# microcontroller_common.net
KiCad netlist of a schematic drawn in Altium Designer
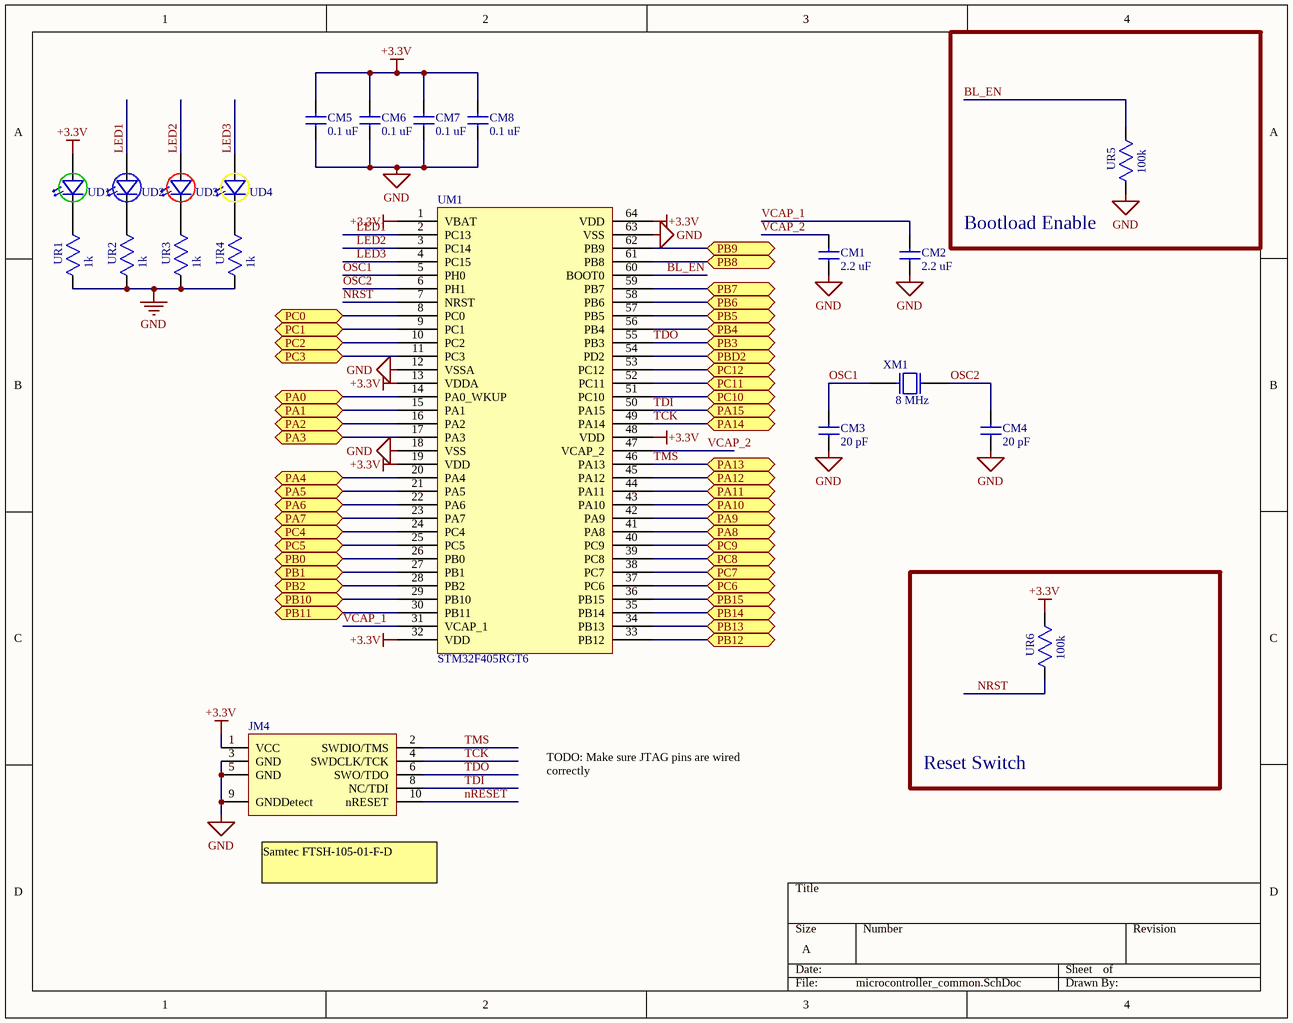
[diagram p0: microcontroller_common.SchDoc]

(export (version "E")
  (design (tool "Eeschema 10.0.6"))
  (components
    (comp (ref "CM1")
      (value "2.2 uF")
      (footprint "0805_Capacitor")
      (description "CAP CERM 2.2 uF")
      (fields (field (name "Comment") "CAP 2.2 uF"))
      (libsource (lib "d1_SchLib") (part "C_0805_2.2uF"))
    )
    (comp (ref "CM2")
      (value "2.2 uF")
      (footprint "0805_Capacitor")
      (description "CAP CERM 2.2 uF")
      (fields (field (name "Comment") "CAP 2.2 uF"))
      (libsource (lib "d1_SchLib") (part "C_0805_2.2uF"))
    )
    (comp (ref "CM3")
      (value "20 pF")
      (footprint "0805_Capacitor")
      (description "CAP CERM 20PF 5% 100V NP0 0805")
      (fields
        (field (name "MANUFACTURER") "AVX")
        (field (name "Comment") "CAP 20PF")
        (field (name "SVP CREATOR") "Jonathan Nutzmann")
      )
      (libsource (lib "d1_SchLib") (part "C_0805_20PF_100V_5%"))
    )
    (comp (ref "CM4")
      (value "20 pF")
      (footprint "0805_Capacitor")
      (description "CAP CERM 20PF 5% 100V NP0 0805")
      (fields
        (field (name "MANUFACTURER") "AVX")
        (field (name "Comment") "CAP 20PF")
        (field (name "SVP CREATOR") "Jonathan Nutzmann")
      )
      (libsource (lib "d1_SchLib") (part "C_0805_20PF_100V_5%"))
    )
    (comp (ref "CM5")
      (value "0.1 uF")
      (footprint "0805_Capacitor")
      (description "CAP CERM 0.1uF")
      (fields
        (field (name "MANUFACTURER") "Yageo")
        (field (name "Comment") "CAP 0.1uF")
        (field (name "SVP CREATOR") "Brett Paulsen")
      )
      (libsource (lib "d1_SchLib") (part "C_0805_0.1uF"))
    )
    (comp (ref "CM6")
      (value "0.1 uF")
      (footprint "0805_Capacitor")
      (description "CAP CERM 0.1uF")
      (fields
        (field (name "MANUFACTURER") "Yageo")
        (field (name "Comment") "CAP 0.1uF")
        (field (name "SVP CREATOR") "Brett Paulsen")
      )
      (libsource (lib "d1_SchLib") (part "C_0805_0.1uF"))
    )
    (comp (ref "CM7")
      (value "0.1 uF")
      (footprint "0805_Capacitor")
      (description "CAP CERM 0.1uF")
      (fields
        (field (name "MANUFACTURER") "Yageo")
        (field (name "Comment") "CAP 0.1uF")
        (field (name "SVP CREATOR") "Brett Paulsen")
      )
      (libsource (lib "d1_SchLib") (part "C_0805_0.1uF"))
    )
    (comp (ref "CM8")
      (value "0.1 uF")
      (footprint "0805_Capacitor")
      (description "CAP CERM 0.1uF")
      (fields
        (field (name "MANUFACTURER") "Yageo")
        (field (name "Comment") "CAP 0.1uF")
        (field (name "SVP CREATOR") "Brett Paulsen")
      )
      (libsource (lib "d1_SchLib") (part "C_0805_0.1uF"))
    )
    (comp (ref "JM4")
      (value "J_CORTEX_DEBUG")
      (footprint "CORTEX_DEBUG")
      (description "CORTEX JTAG DEBUG CONNECTOR")
      (libsource (lib "Nutz") (part "J_CORTEX_DEBUG"))
    )
    (comp (ref "UD1")
      (value "D_LED_0805_GREEN")
      (footprint "0805P_Green")
      (description "LED CHIPLED 570NM GREEN 0805 SMD")
      (fields
        (field (name "MANUFACTURER") "Osram Opto Semiconductors Inc")
        (field (name "SVP CREATOR") "Nate Bolyard")
        (field (name "SVP REVIEWER 1") "Trevtron")
      )
      (libsource (lib "d1_SchLib") (part "D_LED_0805_GREEN"))
    )
    (comp (ref "UD2")
      (value "D_LED_0805_BLUE")
      (footprint "0805_BLUE")
      (description "LED 2X1.2MM 470NM BL WTR CLR SMD")
      (fields (field (name "SVP CREATOR") "Jonathan Nutzmann"))
      (libsource (lib "d1_SchLib") (part "D_LED_0805_BLUE"))
    )
    (comp (ref "UD3")
      (value "D_LED_0805_RED")
      (footprint "0805P_RED")
      (description "LED CHIPLED 645NM RED DIFF 0805")
      (fields (field (name "SVP CREATOR") "Jonathan Nutzmann"))
      (libsource (lib "d1_SchLib") (part "D_LED_0805_RED"))
    )
    (comp (ref "UD4")
      (value "D_LED_0805_YELLOW")
      (footprint "0805P_YELLOW")
      (description "LED 595NM AMBER DIFF SMD 0805")
      (fields (field (name "SVP CREATOR") "Jonathan Nutzmann"))
      (libsource (lib "d1_SchLib") (part "D_LED_0805_YELLOW"))
    )
    (comp (ref "UM1")
      (value "STM32F405RGT6")
      (footprint "STM32_LQFP64")
      (description "IC MCU 32BIT 1MB FLASH 64LQFP")
      (fields (field (name "MANUFACTURER") "STMicroelectronics"))
      (libsource (lib "Nutz") (part "U_STM32F405RGT6"))
    )
    (comp (ref "UR1")
      (value "1k")
      (footprint "0805_Resistor")
      (description "RES 1K OHM 1/8W 1% 0805 SMD")
      (fields (field (name "Comment") "R_0805_1k") (field (name "SVP CREATOR") "Katie Moenkhaus"))
      (libsource (lib "d1_SchLib") (part "R_0805_1K_1%"))
    )
    (comp (ref "UR2")
      (value "1k")
      (footprint "0805_Resistor")
      (description "RES 1K OHM 1/8W 1% 0805 SMD")
      (fields (field (name "Comment") "R_0805_1k") (field (name "SVP CREATOR") "Katie Moenkhaus"))
      (libsource (lib "d1_SchLib") (part "R_0805_1K_1%"))
    )
    (comp (ref "UR3")
      (value "1k")
      (footprint "0805_Resistor")
      (description "RES 1K OHM 1/8W 1% 0805 SMD")
      (fields (field (name "Comment") "R_0805_1k") (field (name "SVP CREATOR") "Katie Moenkhaus"))
      (libsource (lib "d1_SchLib") (part "R_0805_1K_1%"))
    )
    (comp (ref "UR4")
      (value "1k")
      (footprint "0805_Resistor")
      (description "RES 1K OHM 1/8W 1% 0805 SMD")
      (fields (field (name "Comment") "R_0805_1k") (field (name "SVP CREATOR") "Katie Moenkhaus"))
      (libsource (lib "d1_SchLib") (part "R_0805_1K_1%"))
    )
    (comp (ref "UR5")
      (value "100k")
      (footprint "0805_Resistor")
      (description "RES 100K OHM 1/8W 1% 0805 SMD")
      (fields
        (field (name "MANUFACTURER") "Rohm Semiconductor")
        (field (name "Comment") "R_0805_100k_1%")
        (field (name "SVP CREATOR") "Jonathan Nutzmann")
      )
      (libsource (lib "d1_SchLib") (part "R_0805_100k_1%"))
    )
    (comp (ref "UR6")
      (value "100k")
      (footprint "0805_Resistor")
      (description "RES 100K OHM 1/8W 1% 0805 SMD")
      (fields
        (field (name "MANUFACTURER") "Rohm Semiconductor")
        (field (name "Comment") "R_0805_100k_1%")
        (field (name "SVP CREATOR") "Jonathan Nutzmann")
      )
      (libsource (lib "d1_SchLib") (part "R_0805_100k_1%"))
    )
    (comp (ref "XM1")
      (value "8 MHz")
      (footprint "HC-49")
      (description "CRYSTAL 8.00 MHZ 20PF 49US")
      (fields
        (field (name "MANUFACTURER") "ECS")
        (field (name "Comment") "HC49")
        (field (name "SVP CREATOR") "Jonathan Nutzmann")
      )
      (libsource (lib "d1_SchLib") (part "X_HC49"))
    )
  )
  (nets
    (net (code "1") (name "+3.3V") (class "Default")
      (node (ref "CM5") (pin "1") (pinfunction "1_1") (pintype "passive"))
      (node (ref "CM6") (pin "1") (pinfunction "1_1") (pintype "passive"))
      (node (ref "CM7") (pin "1") (pinfunction "1_1") (pintype "passive"))
      (node (ref "CM8") (pin "1") (pinfunction "1_1") (pintype "passive"))
      (node (ref "JM4") (pin "1") (pinfunction "VCC_1") (pintype "passive"))
      (node (ref "UD1") (pin "2") (pinfunction "Anode_2") (pintype "passive"))
      (node (ref "UM1") (pin "1") (pinfunction "VBAT_1") (pintype "passive"))
      (node (ref "UM1") (pin "13") (pinfunction "VDDA_13") (pintype "passive"))
      (node (ref "UM1") (pin "19") (pinfunction "VDD_19") (pintype "passive"))
      (node (ref "UM1") (pin "32") (pinfunction "VDD_32") (pintype "passive"))
      (node (ref "UM1") (pin "48") (pinfunction "VDD_48") (pintype "passive"))
      (node (ref "UM1") (pin "64") (pinfunction "VDD_64") (pintype "passive"))
      (node (ref "UR6") (pin "1") (pinfunction "1_1") (pintype "passive"))
    )
    (net (code "2") (name "/BL_EN") (class "Default")
      (node (ref "UM1") (pin "60") (pinfunction "BOOT0_60") (pintype "passive"))
      (node (ref "UR5") (pin "1") (pinfunction "1_1") (pintype "passive"))
    )
    (net (code "3") (name "/LED1") (class "Default")
      (node (ref "UD2") (pin "2") (pinfunction "Anode_2") (pintype "passive"))
      (node (ref "UM1") (pin "2") (pinfunction "PC13_2") (pintype "passive"))
    )
    (net (code "4") (name "/LED2") (class "Default")
      (node (ref "UD3") (pin "2") (pinfunction "Anode_2") (pintype "passive"))
      (node (ref "UM1") (pin "3") (pinfunction "PC14_3") (pintype "passive"))
    )
    (net (code "5") (name "/LED3") (class "Default")
      (node (ref "UD4") (pin "2") (pinfunction "Anode_2") (pintype "passive"))
      (node (ref "UM1") (pin "4") (pinfunction "PC15_4") (pintype "passive"))
    )
    (net (code "6") (name "/NRST") (class "Default")
      (node (ref "UM1") (pin "7") (pinfunction "NRST_7") (pintype "passive"))
      (node (ref "UR6") (pin "2") (pinfunction "2_2") (pintype "passive"))
    )
    (net (code "7") (name "/OSC1") (class "Default")
      (node (ref "CM3") (pin "1") (pinfunction "1_1") (pintype "passive"))
      (node (ref "UM1") (pin "5") (pinfunction "PH0_5") (pintype "passive"))
      (node (ref "XM1") (pin "1") (pinfunction "1_1") (pintype "passive"))
    )
    (net (code "8") (name "/OSC2") (class "Default")
      (node (ref "CM4") (pin "1") (pinfunction "1_1") (pintype "passive"))
      (node (ref "UM1") (pin "6") (pinfunction "PH1_6") (pintype "passive"))
      (node (ref "XM1") (pin "2") (pinfunction "2_2") (pintype "passive"))
    )
    (net (code "9") (name "/PA0") (class "Default")
      (node (ref "UM1") (pin "14") (pinfunction "PA0_WKUP_14") (pintype "passive"))
    )
    (net (code "10") (name "/PA1") (class "Default")
      (node (ref "UM1") (pin "15") (pinfunction "PA1_15") (pintype "passive"))
    )
    (net (code "11") (name "/PA2") (class "Default")
      (node (ref "UM1") (pin "16") (pinfunction "PA2_16") (pintype "passive"))
    )
    (net (code "12") (name "/PA3") (class "Default")
      (node (ref "UM1") (pin "17") (pinfunction "PA3_17") (pintype "passive"))
    )
    (net (code "13") (name "/PA4") (class "Default")
      (node (ref "UM1") (pin "20") (pinfunction "PA4_20") (pintype "passive"))
    )
    (net (code "14") (name "/PA5") (class "Default")
      (node (ref "UM1") (pin "21") (pinfunction "PA5_21") (pintype "passive"))
    )
    (net (code "15") (name "/PA6") (class "Default")
      (node (ref "UM1") (pin "22") (pinfunction "PA6_22") (pintype "passive"))
    )
    (net (code "16") (name "/PA7") (class "Default")
      (node (ref "UM1") (pin "23") (pinfunction "PA7_23") (pintype "passive"))
    )
    (net (code "17") (name "/PA8") (class "Default")
      (node (ref "UM1") (pin "41") (pinfunction "PA8_41") (pintype "passive"))
    )
    (net (code "18") (name "/PA9") (class "Default")
      (node (ref "UM1") (pin "42") (pinfunction "PA9_42") (pintype "passive"))
    )
    (net (code "19") (name "/PA10") (class "Default")
      (node (ref "UM1") (pin "43") (pinfunction "PA10_43") (pintype "passive"))
    )
    (net (code "20") (name "/PA11") (class "Default")
      (node (ref "UM1") (pin "44") (pinfunction "PA11_44") (pintype "passive"))
    )
    (net (code "21") (name "/PA12") (class "Default")
      (node (ref "UM1") (pin "45") (pinfunction "PA12_45") (pintype "passive"))
    )
    (net (code "22") (name "/PB0") (class "Default")
      (node (ref "UM1") (pin "26") (pinfunction "PB0_26") (pintype "passive"))
    )
    (net (code "23") (name "/PB1") (class "Default")
      (node (ref "UM1") (pin "27") (pinfunction "PB1_27") (pintype "passive"))
    )
    (net (code "24") (name "/PB2") (class "Default")
      (node (ref "UM1") (pin "28") (pinfunction "PB2_28") (pintype "passive"))
    )
    (net (code "25") (name "/PB4") (class "Default")
      (node (ref "UM1") (pin "56") (pinfunction "PB4_56") (pintype "passive"))
    )
    (net (code "26") (name "/PB5") (class "Default")
      (node (ref "UM1") (pin "57") (pinfunction "PB5_57") (pintype "passive"))
    )
    (net (code "27") (name "/PB6") (class "Default")
      (node (ref "UM1") (pin "58") (pinfunction "PB6_58") (pintype "passive"))
    )
    (net (code "28") (name "/PB7") (class "Default")
      (node (ref "UM1") (pin "59") (pinfunction "PB7_59") (pintype "passive"))
    )
    (net (code "29") (name "/PB8") (class "Default")
      (node (ref "UM1") (pin "61") (pinfunction "PB8_61") (pintype "passive"))
    )
    (net (code "30") (name "/PB9") (class "Default")
      (node (ref "UM1") (pin "62") (pinfunction "PB9_62") (pintype "passive"))
    )
    (net (code "31") (name "/PB10") (class "Default")
      (node (ref "UM1") (pin "29") (pinfunction "PB10_29") (pintype "passive"))
    )
    (net (code "32") (name "/PB11") (class "Default")
      (node (ref "UM1") (pin "30") (pinfunction "PB11_30") (pintype "passive"))
    )
    (net (code "33") (name "/PB12") (class "Default")
      (node (ref "UM1") (pin "33") (pinfunction "PB12_33") (pintype "passive"))
    )
    (net (code "34") (name "/PB13") (class "Default")
      (node (ref "UM1") (pin "34") (pinfunction "PB13_34") (pintype "passive"))
    )
    (net (code "35") (name "/PB14") (class "Default")
      (node (ref "UM1") (pin "35") (pinfunction "PB14_35") (pintype "passive"))
    )
    (net (code "36") (name "/PB15") (class "Default")
      (node (ref "UM1") (pin "36") (pinfunction "PB15_36") (pintype "passive"))
    )
    (net (code "37") (name "/PBD2") (class "Default")
      (node (ref "UM1") (pin "54") (pinfunction "PD2_54") (pintype "passive"))
    )
    (net (code "38") (name "/PC0") (class "Default")
      (node (ref "UM1") (pin "8") (pinfunction "PC0_8") (pintype "passive"))
    )
    (net (code "39") (name "/PC1") (class "Default")
      (node (ref "UM1") (pin "9") (pinfunction "PC1_9") (pintype "passive"))
    )
    (net (code "40") (name "/PC2") (class "Default")
      (node (ref "UM1") (pin "10") (pinfunction "PC2_10") (pintype "passive"))
    )
    (net (code "41") (name "/PC3") (class "Default")
      (node (ref "UM1") (pin "11") (pinfunction "PC3_11") (pintype "passive"))
    )
    (net (code "42") (name "/PC4") (class "Default")
      (node (ref "UM1") (pin "24") (pinfunction "PC4_24") (pintype "passive"))
    )
    (net (code "43") (name "/PC5") (class "Default")
      (node (ref "UM1") (pin "25") (pinfunction "PC5_25") (pintype "passive"))
    )
    (net (code "44") (name "/PC6") (class "Default")
      (node (ref "UM1") (pin "37") (pinfunction "PC6_37") (pintype "passive"))
    )
    (net (code "45") (name "/PC7") (class "Default")
      (node (ref "UM1") (pin "38") (pinfunction "PC7_38") (pintype "passive"))
    )
    (net (code "46") (name "/PC8") (class "Default")
      (node (ref "UM1") (pin "39") (pinfunction "PC8_39") (pintype "passive"))
    )
    (net (code "47") (name "/PC9") (class "Default")
      (node (ref "UM1") (pin "40") (pinfunction "PC9_40") (pintype "passive"))
    )
    (net (code "48") (name "/PC10") (class "Default")
      (node (ref "UM1") (pin "51") (pinfunction "PC10_51") (pintype "passive"))
    )
    (net (code "49") (name "/PC11") (class "Default")
      (node (ref "UM1") (pin "52") (pinfunction "PC11_52") (pintype "passive"))
    )
    (net (code "50") (name "/PC12") (class "Default")
      (node (ref "UM1") (pin "53") (pinfunction "PC12_53") (pintype "passive"))
    )
    (net (code "51") (name "/TCK") (class "Default")
      (node (ref "JM4") (pin "4") (pinfunction "SWDCLK/TCK_4") (pintype "passive"))
      (node (ref "UM1") (pin "49") (pinfunction "PA14_49") (pintype "passive"))
    )
    (net (code "52") (name "/TDI") (class "Default")
      (node (ref "JM4") (pin "8") (pinfunction "NC/TDI_8") (pintype "passive"))
      (node (ref "UM1") (pin "50") (pinfunction "PA15_50") (pintype "passive"))
    )
    (net (code "53") (name "/TDO") (class "Default")
      (node (ref "JM4") (pin "6") (pinfunction "SWO/TDO_6") (pintype "passive"))
      (node (ref "UM1") (pin "55") (pinfunction "PB3_55") (pintype "passive"))
    )
    (net (code "54") (name "/TMS") (class "Default")
      (node (ref "JM4") (pin "2") (pinfunction "SWDIO/TMS_2") (pintype "passive"))
      (node (ref "UM1") (pin "46") (pinfunction "PA13_46") (pintype "passive"))
    )
    (net (code "55") (name "/VCAP_1") (class "Default")
      (node (ref "CM2") (pin "1") (pinfunction "1_1") (pintype "passive"))
      (node (ref "UM1") (pin "31") (pinfunction "VCAP_1_31") (pintype "passive"))
    )
    (net (code "56") (name "/VCAP_2") (class "Default")
      (node (ref "CM1") (pin "1") (pinfunction "1_1") (pintype "passive"))
      (node (ref "UM1") (pin "47") (pinfunction "VCAP_2_47") (pintype "passive"))
    )
    (net (code "57") (name "/nRESET") (class "Default")
      (node (ref "JM4") (pin "10") (pinfunction "nRESET_10") (pintype "passive"))
    )
    (net (code "58") (name "GND") (class "Default")
      (node (ref "CM1") (pin "2") (pinfunction "2_2") (pintype "passive"))
      (node (ref "CM2") (pin "2") (pinfunction "2_2") (pintype "passive"))
      (node (ref "CM3") (pin "2") (pinfunction "2_2") (pintype "passive"))
      (node (ref "CM4") (pin "2") (pinfunction "2_2") (pintype "passive"))
      (node (ref "CM5") (pin "2") (pinfunction "2_2") (pintype "passive"))
      (node (ref "CM6") (pin "2") (pinfunction "2_2") (pintype "passive"))
      (node (ref "CM7") (pin "2") (pinfunction "2_2") (pintype "passive"))
      (node (ref "CM8") (pin "2") (pinfunction "2_2") (pintype "passive"))
      (node (ref "JM4") (pin "3") (pinfunction "GND_3") (pintype "passive"))
      (node (ref "JM4") (pin "5") (pinfunction "GND_5") (pintype "passive"))
      (node (ref "JM4") (pin "9") (pinfunction "GNDDetect_9") (pintype "passive"))
      (node (ref "UM1") (pin "12") (pinfunction "VSSA_12") (pintype "passive"))
      (node (ref "UM1") (pin "18") (pinfunction "VSS_18") (pintype "passive"))
      (node (ref "UM1") (pin "63") (pinfunction "VSS_63") (pintype "passive"))
      (node (ref "UR1") (pin "2") (pinfunction "2_2") (pintype "passive"))
      (node (ref "UR2") (pin "2") (pinfunction "2_2") (pintype "passive"))
      (node (ref "UR3") (pin "2") (pinfunction "2_2") (pintype "passive"))
      (node (ref "UR4") (pin "2") (pinfunction "2_2") (pintype "passive"))
      (node (ref "UR5") (pin "2") (pinfunction "2_2") (pintype "passive"))
    )
    (net (code "59") (name "Net-(UD1-Cathode)") (class "Default")
      (node (ref "UD1") (pin "1") (pinfunction "Cathode_1") (pintype "passive"))
      (node (ref "UR1") (pin "1") (pinfunction "1_1") (pintype "passive"))
    )
    (net (code "60") (name "Net-(UD2-Cathode)") (class "Default")
      (node (ref "UD2") (pin "1") (pinfunction "Cathode_1") (pintype "passive"))
      (node (ref "UR2") (pin "1") (pinfunction "1_1") (pintype "passive"))
    )
    (net (code "61") (name "Net-(UD3-Cathode)") (class "Default")
      (node (ref "UD3") (pin "1") (pinfunction "Cathode_1") (pintype "passive"))
      (node (ref "UR3") (pin "1") (pinfunction "1_1") (pintype "passive"))
    )
    (net (code "62") (name "Net-(UD4-Cathode)") (class "Default")
      (node (ref "UD4") (pin "1") (pinfunction "Cathode_1") (pintype "passive"))
      (node (ref "UR4") (pin "1") (pinfunction "1_1") (pintype "passive"))
    )
  )
)
